# design.net
KiCad netlist of a schematic drawn in Altium Designer
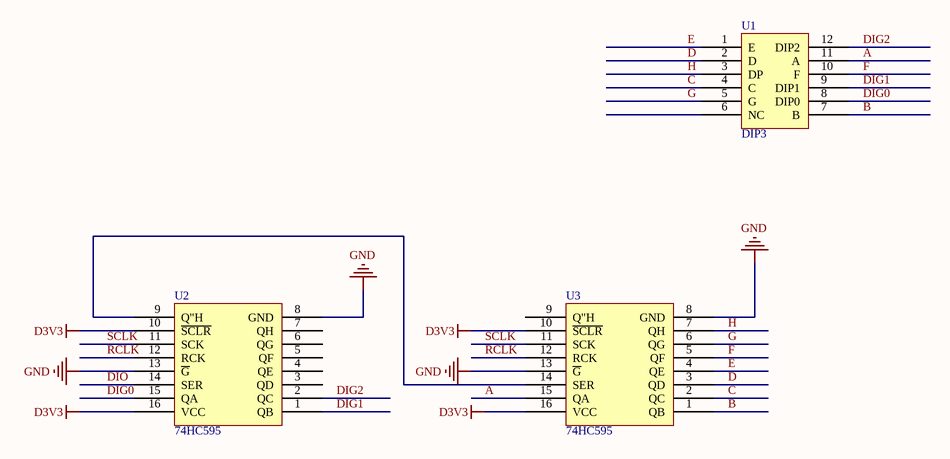
[diagram p0: 显示.SchDoc]

(export (version "E")
  (design (tool "Eeschema 10.0.6"))
  (components
    (comp (ref "U1") (value "DIP3") (footprint "DIP3") (libsource (lib "DX") (part "DIP3")))
    (comp (ref "U2") (value "74HC595") (footprint "LC-SOP-16_150mil") (libsource (lib "DX") (part "74HC595")))
    (comp (ref "U3") (value "74HC595") (footprint "LC-SOP-16_150mil") (libsource (lib "DX") (part "74HC595")))
  )
  (nets
    (net (code "1") (name "/A") (class "Default")
      (node (ref "U1") (pin "11") (pinfunction "A_11") (pintype "passive"))
      (node (ref "U3") (pin "15") (pinfunction "QA_15") (pintype "passive"))
    )
    (net (code "2") (name "/B") (class "Default")
      (node (ref "U1") (pin "7") (pinfunction "B_7") (pintype "passive"))
      (node (ref "U3") (pin "1") (pinfunction "QB_1") (pintype "passive"))
    )
    (net (code "3") (name "/C") (class "Default")
      (node (ref "U1") (pin "4") (pinfunction "C_4") (pintype "passive"))
      (node (ref "U3") (pin "2") (pinfunction "QC_2") (pintype "passive"))
    )
    (net (code "4") (name "/D") (class "Default")
      (node (ref "U1") (pin "2") (pinfunction "D_2") (pintype "passive"))
      (node (ref "U3") (pin "3") (pinfunction "QD_3") (pintype "passive"))
    )
    (net (code "5") (name "/DIG0") (class "Default")
      (node (ref "U1") (pin "8") (pinfunction "DIP0_8") (pintype "passive"))
      (node (ref "U2") (pin "15") (pinfunction "QA_15") (pintype "passive"))
    )
    (net (code "6") (name "/DIG1") (class "Default")
      (node (ref "U1") (pin "9") (pinfunction "DIP1_9") (pintype "passive"))
      (node (ref "U2") (pin "1") (pinfunction "QB_1") (pintype "passive"))
    )
    (net (code "7") (name "/DIG2") (class "Default")
      (node (ref "U1") (pin "12") (pinfunction "DIP2_12") (pintype "passive"))
      (node (ref "U2") (pin "2") (pinfunction "QC_2") (pintype "passive"))
    )
    (net (code "8") (name "/DIO") (class "Default")
      (node (ref "U2") (pin "14") (pinfunction "SER_14") (pintype "passive"))
    )
    (net (code "9") (name "/E") (class "Default")
      (node (ref "U1") (pin "1") (pinfunction "E_1") (pintype "passive"))
      (node (ref "U3") (pin "4") (pinfunction "QE_4") (pintype "passive"))
    )
    (net (code "10") (name "/F") (class "Default")
      (node (ref "U1") (pin "10") (pinfunction "F_10") (pintype "passive"))
      (node (ref "U3") (pin "5") (pinfunction "QF_5") (pintype "passive"))
    )
    (net (code "11") (name "/G") (class "Default")
      (node (ref "U1") (pin "5") (pinfunction "G_5") (pintype "passive"))
      (node (ref "U3") (pin "6") (pinfunction "QG_6") (pintype "passive"))
    )
    (net (code "12") (name "/H") (class "Default")
      (node (ref "U1") (pin "3") (pinfunction "DP_3") (pintype "passive"))
      (node (ref "U3") (pin "7") (pinfunction "QH_7") (pintype "passive"))
    )
    (net (code "13") (name "/RCLK") (class "Default")
      (node (ref "U2") (pin "12") (pinfunction "RCK_12") (pintype "passive"))
      (node (ref "U3") (pin "12") (pinfunction "RCK_12") (pintype "passive"))
    )
    (net (code "14") (name "/SCLK") (class "Default")
      (node (ref "U2") (pin "11") (pinfunction "SCK_11") (pintype "passive"))
      (node (ref "U3") (pin "11") (pinfunction "SCK_11") (pintype "passive"))
    )
    (net (code "15") (name "D3V3") (class "Default")
      (node (ref "U2") (pin "10") (pinfunction "~{SCLR}_10") (pintype "passive"))
      (node (ref "U2") (pin "16") (pinfunction "VCC_16") (pintype "passive"))
      (node (ref "U3") (pin "10") (pinfunction "~{SCLR}_10") (pintype "passive"))
      (node (ref "U3") (pin "16") (pinfunction "VCC_16") (pintype "passive"))
    )
    (net (code "16") (name "GND") (class "Default")
      (node (ref "U2") (pin "13") (pinfunction "~{G}_13") (pintype "passive"))
      (node (ref "U2") (pin "8") (pinfunction "GND_8") (pintype "passive"))
      (node (ref "U3") (pin "13") (pinfunction "~{G}_13") (pintype "passive"))
      (node (ref "U3") (pin "8") (pinfunction "GND_8") (pintype "passive"))
    )
    (net (code "17") (name "Net-(U2-Q\"H)") (class "Default")
      (node (ref "U2") (pin "9") (pinfunction "Q\"H_9") (pintype "passive"))
      (node (ref "U3") (pin "14") (pinfunction "SER_14") (pintype "passive"))
    )
    (net (code "18") (name "unconnected-(U1-NC-Pad6)") (class "Default")
      (node (ref "U1") (pin "6") (pinfunction "NC_6") (pintype "passive"))
    )
    (net (code "19") (name "unconnected-(U2-QD-Pad3)") (class "Default")
      (node (ref "U2") (pin "3") (pinfunction "QD_3") (pintype "passive"))
    )
    (net (code "20") (name "unconnected-(U2-QE-Pad4)") (class "Default")
      (node (ref "U2") (pin "4") (pinfunction "QE_4") (pintype "passive"))
    )
    (net (code "21") (name "unconnected-(U2-QF-Pad5)") (class "Default")
      (node (ref "U2") (pin "5") (pinfunction "QF_5") (pintype "passive"))
    )
    (net (code "22") (name "unconnected-(U2-QG-Pad6)") (class "Default")
      (node (ref "U2") (pin "6") (pinfunction "QG_6") (pintype "passive"))
    )
    (net (code "23") (name "unconnected-(U2-QH-Pad7)") (class "Default")
      (node (ref "U2") (pin "7") (pinfunction "QH_7") (pintype "passive"))
    )
    (net (code "24") (name "unconnected-(U3-Q\"H-Pad9)") (class "Default")
      (node (ref "U3") (pin "9") (pinfunction "Q\"H_9") (pintype "passive"))
    )
  )
)
